# switch-rev2.net
KiCad netlist of a schematic drawn in EAGLE
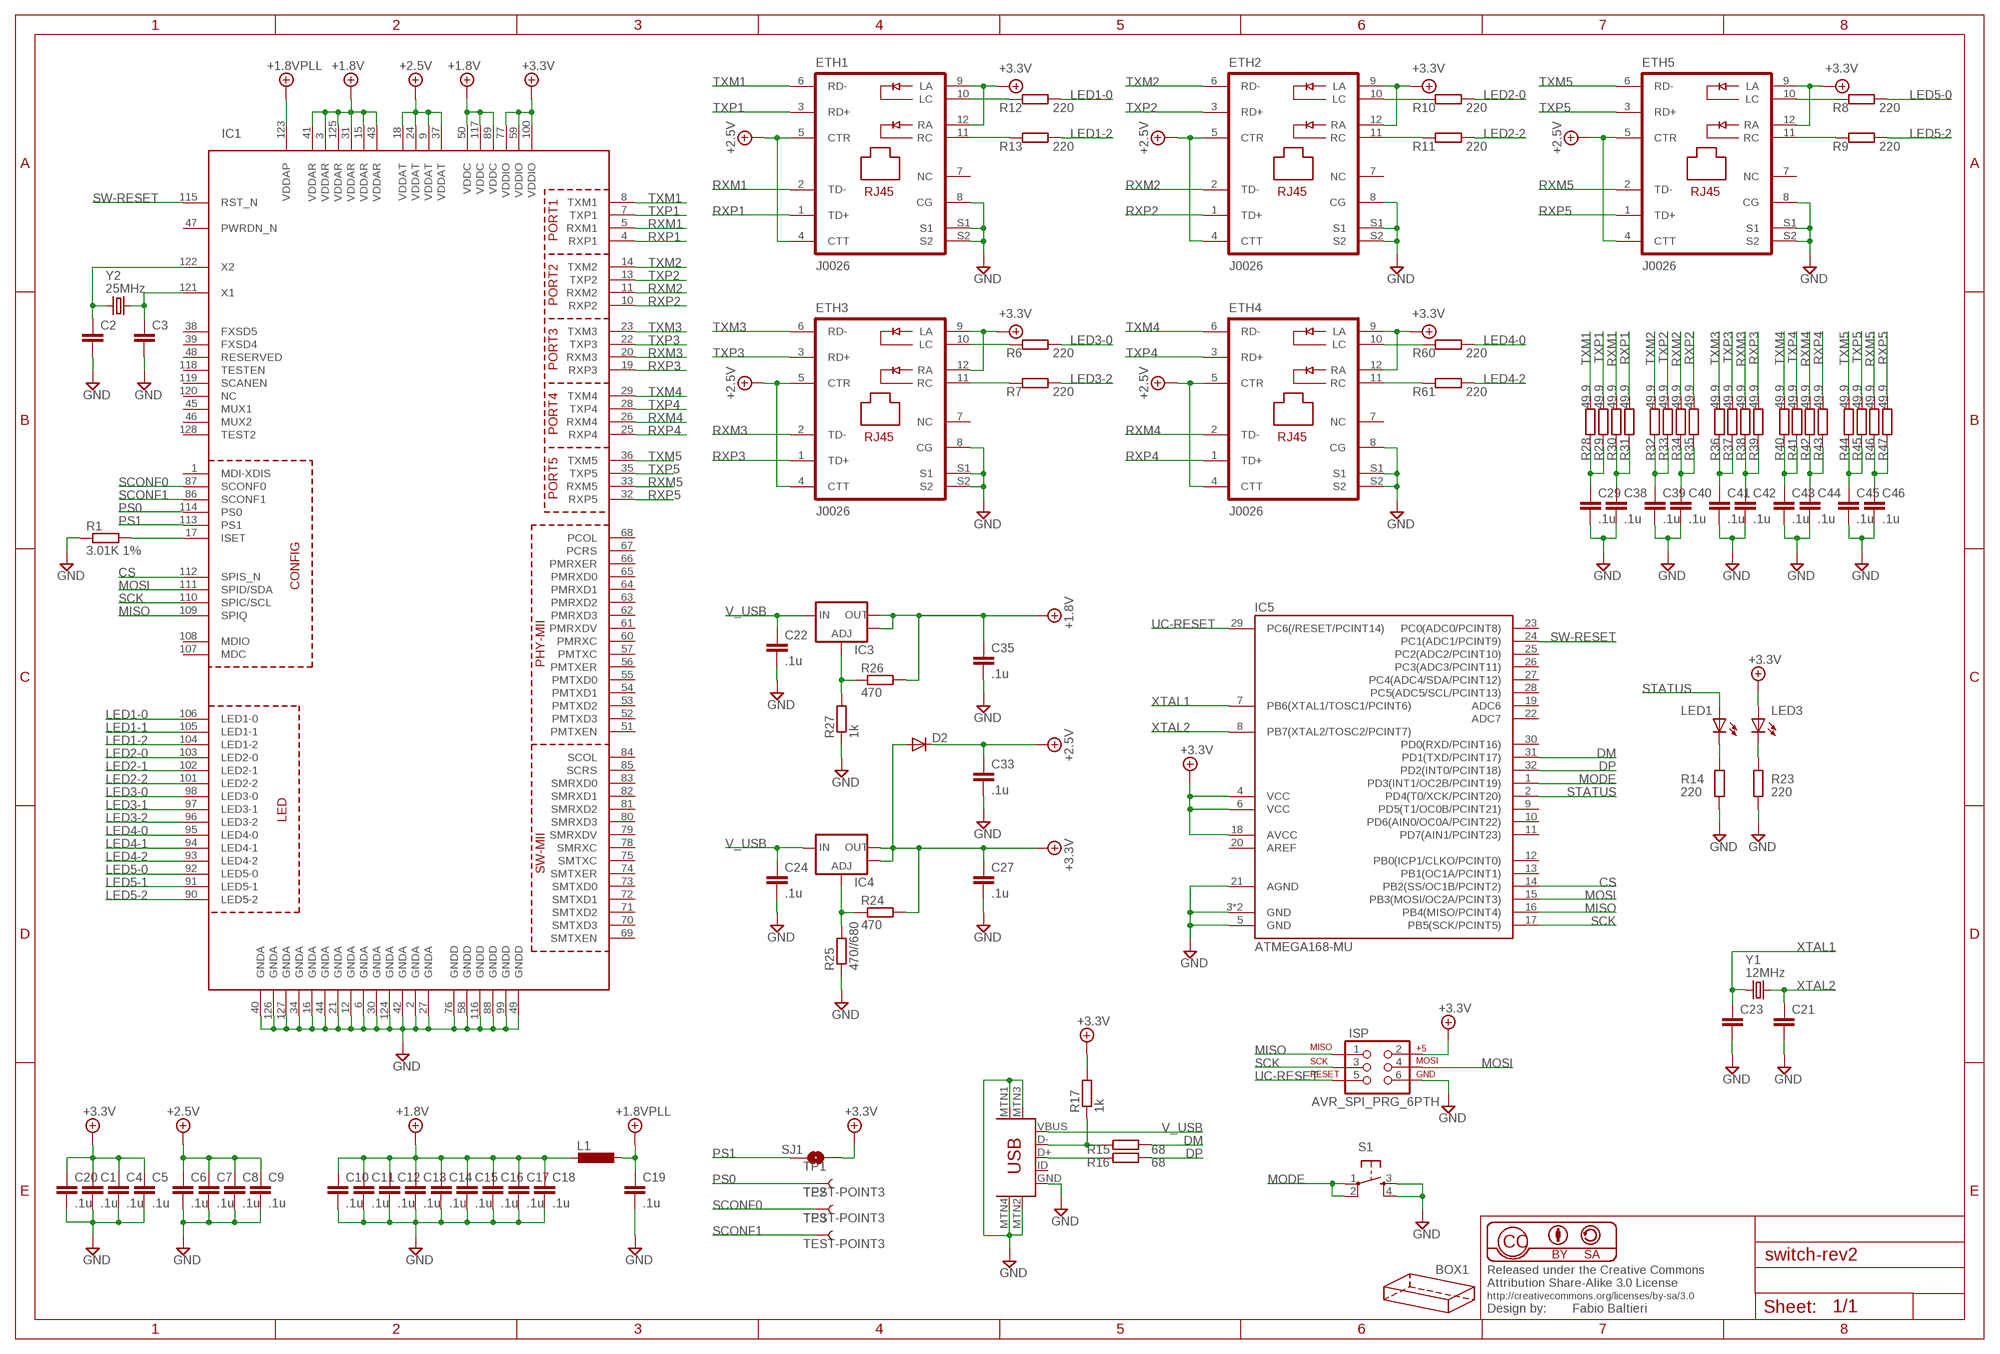
[diagram p0: schematic, sheet 1]

(export (version "E")
  (design (tool "Eeschema 10.0.6"))
  (components
    (comp (ref "BOX1")
      (value "HAMMOND-BOX-XXA")
      (footprint "eagle-import:1591XXA")
      (libsource (lib "eagle-import") (part "HAMMOND-BOX-XXA"))
    )
    (comp (ref "C1")
      (value ".1u")
      (footprint "eagle-import:C0805")
      (libsource (lib "eagle-import") (part "C-EUC0805"))
    )
    (comp (ref "C2")
      (value "C-EUC0805")
      (footprint "eagle-import:C0805")
      (libsource (lib "eagle-import") (part "C-EUC0805"))
    )
    (comp (ref "C3")
      (value "C-EUC0805")
      (footprint "eagle-import:C0805")
      (libsource (lib "eagle-import") (part "C-EUC0805"))
    )
    (comp (ref "C4")
      (value ".1u")
      (footprint "eagle-import:C0805")
      (libsource (lib "eagle-import") (part "C-EUC0805"))
    )
    (comp (ref "C5")
      (value ".1u")
      (footprint "eagle-import:C0805")
      (libsource (lib "eagle-import") (part "C-EUC0805"))
    )
    (comp (ref "C6")
      (value ".1u")
      (footprint "eagle-import:C0805")
      (libsource (lib "eagle-import") (part "C-EUC0805"))
    )
    (comp (ref "C7")
      (value ".1u")
      (footprint "eagle-import:C0805")
      (libsource (lib "eagle-import") (part "C-EUC0805"))
    )
    (comp (ref "C8")
      (value ".1u")
      (footprint "eagle-import:C0805")
      (libsource (lib "eagle-import") (part "C-EUC0805"))
    )
    (comp (ref "C9")
      (value ".1u")
      (footprint "eagle-import:C0805")
      (libsource (lib "eagle-import") (part "C-EUC0805"))
    )
    (comp (ref "C10")
      (value ".1u")
      (footprint "eagle-import:C0805")
      (libsource (lib "eagle-import") (part "C-EUC0805"))
    )
    (comp (ref "C11")
      (value ".1u")
      (footprint "eagle-import:C0805")
      (libsource (lib "eagle-import") (part "C-EUC0805"))
    )
    (comp (ref "C12")
      (value ".1u")
      (footprint "eagle-import:C0805")
      (libsource (lib "eagle-import") (part "C-EUC0805"))
    )
    (comp (ref "C13")
      (value ".1u")
      (footprint "eagle-import:C0805")
      (libsource (lib "eagle-import") (part "C-EUC0805"))
    )
    (comp (ref "C14")
      (value ".1u")
      (footprint "eagle-import:C0805")
      (libsource (lib "eagle-import") (part "C-EUC0805"))
    )
    (comp (ref "C15")
      (value ".1u")
      (footprint "eagle-import:C0805")
      (libsource (lib "eagle-import") (part "C-EUC0805"))
    )
    (comp (ref "C16")
      (value ".1u")
      (footprint "eagle-import:C0805")
      (libsource (lib "eagle-import") (part "C-EUC0805"))
    )
    (comp (ref "C17")
      (value ".1u")
      (footprint "eagle-import:C0805")
      (libsource (lib "eagle-import") (part "C-EUC0805"))
    )
    (comp (ref "C18")
      (value ".1u")
      (footprint "eagle-import:C0805")
      (libsource (lib "eagle-import") (part "C-EUC0805"))
    )
    (comp (ref "C19")
      (value ".1u")
      (footprint "eagle-import:C0805")
      (libsource (lib "eagle-import") (part "C-EUC0805"))
    )
    (comp (ref "C20")
      (value ".1u")
      (footprint "eagle-import:C0805")
      (libsource (lib "eagle-import") (part "C-EUC0805"))
    )
    (comp (ref "C21")
      (value "C-EUC0805")
      (footprint "eagle-import:C0805")
      (libsource (lib "eagle-import") (part "C-EUC0805"))
    )
    (comp (ref "C22")
      (value ".1u")
      (footprint "eagle-import:C0805")
      (libsource (lib "eagle-import") (part "C-EUC0805"))
    )
    (comp (ref "C23")
      (value "C-EUC0805")
      (footprint "eagle-import:C0805")
      (libsource (lib "eagle-import") (part "C-EUC0805"))
    )
    (comp (ref "C24")
      (value ".1u")
      (footprint "eagle-import:C0805")
      (libsource (lib "eagle-import") (part "C-EUC0805"))
    )
    (comp (ref "C27")
      (value ".1u")
      (footprint "eagle-import:C0805")
      (libsource (lib "eagle-import") (part "C-EUC0805"))
    )
    (comp (ref "C29")
      (value ".1u")
      (footprint "eagle-import:C0805")
      (libsource (lib "eagle-import") (part "C-EUC0805"))
    )
    (comp (ref "C33")
      (value ".1u")
      (footprint "eagle-import:C0805")
      (libsource (lib "eagle-import") (part "C-EUC0805"))
    )
    (comp (ref "C35")
      (value ".1u")
      (footprint "eagle-import:C0805")
      (libsource (lib "eagle-import") (part "C-EUC0805"))
    )
    (comp (ref "C38")
      (value ".1u")
      (footprint "eagle-import:C0805")
      (libsource (lib "eagle-import") (part "C-EUC0805"))
    )
    (comp (ref "C39")
      (value ".1u")
      (footprint "eagle-import:C0805")
      (libsource (lib "eagle-import") (part "C-EUC0805"))
    )
    (comp (ref "C40")
      (value ".1u")
      (footprint "eagle-import:C0805")
      (libsource (lib "eagle-import") (part "C-EUC0805"))
    )
    (comp (ref "C41")
      (value ".1u")
      (footprint "eagle-import:C0805")
      (libsource (lib "eagle-import") (part "C-EUC0805"))
    )
    (comp (ref "C42")
      (value ".1u")
      (footprint "eagle-import:C0805")
      (libsource (lib "eagle-import") (part "C-EUC0805"))
    )
    (comp (ref "C43")
      (value ".1u")
      (footprint "eagle-import:C0805")
      (libsource (lib "eagle-import") (part "C-EUC0805"))
    )
    (comp (ref "C44")
      (value ".1u")
      (footprint "eagle-import:C0805")
      (libsource (lib "eagle-import") (part "C-EUC0805"))
    )
    (comp (ref "C45")
      (value ".1u")
      (footprint "eagle-import:C0805")
      (libsource (lib "eagle-import") (part "C-EUC0805"))
    )
    (comp (ref "C46")
      (value ".1u")
      (footprint "eagle-import:C0805")
      (libsource (lib "eagle-import") (part "C-EUC0805"))
    )
    (comp (ref "D2")
      (value "DIODE-SMB")
      (footprint "eagle-import:SMB")
      (libsource (lib "eagle-import") (part "DIODE-SMB"))
    )
    (comp (ref "ETH1")
      (value "J0026")
      (footprint "eagle-import:PJ-J0")
      (libsource (lib "eagle-import") (part "J0026"))
    )
    (comp (ref "ETH2")
      (value "J0026")
      (footprint "eagle-import:PJ-J0")
      (libsource (lib "eagle-import") (part "J0026"))
    )
    (comp (ref "ETH3")
      (value "J0026")
      (footprint "eagle-import:PJ-J0")
      (libsource (lib "eagle-import") (part "J0026"))
    )
    (comp (ref "ETH4")
      (value "J0026")
      (footprint "eagle-import:PJ-J0")
      (libsource (lib "eagle-import") (part "J0026"))
    )
    (comp (ref "ETH5")
      (value "J0026")
      (footprint "eagle-import:PJ-J0")
      (libsource (lib "eagle-import") (part "J0026"))
    )
    (comp (ref "IC1")
      (value "KS8995MA")
      (footprint "eagle-import:PQFP128L")
      (libsource (lib "eagle-import") (part "KS8995MA"))
    )
    (comp (ref "IC3")
      (value "V_REG_LM1117SOT223")
      (footprint "eagle-import:SOT223")
      (libsource (lib "eagle-import") (part "V_REG_LM1117SOT223"))
    )
    (comp (ref "IC4")
      (value "V_REG_LM1117SOT223")
      (footprint "eagle-import:SOT223")
      (libsource (lib "eagle-import") (part "V_REG_LM1117SOT223"))
    )
    (comp (ref "IC5")
      (value "ATMEGA168-MU")
      (footprint "eagle-import:MLF32-TH")
      (libsource (lib "eagle-import") (part "ATMEGA168-MU"))
    )
    (comp (ref "ISP")
      (value "AVR_SPI_PRG_6PTH")
      (footprint "eagle-import:2X3")
      (libsource (lib "eagle-import") (part "AVR_SPI_PRG_6PTH"))
    )
    (comp (ref "L1")
      (value "L-EUL2012C")
      (footprint "eagle-import:L2012C")
      (libsource (lib "eagle-import") (part "L-EUL2012C"))
    )
    (comp (ref "LED1")
      (value "LEDCHIPLED_0603")
      (footprint "eagle-import:CHIPLED_0603")
      (libsource (lib "eagle-import") (part "LEDCHIPLED_0603"))
    )
    (comp (ref "LED3")
      (value "LEDCHIPLED_0603")
      (footprint "eagle-import:CHIPLED_0603")
      (libsource (lib "eagle-import") (part "LEDCHIPLED_0603"))
    )
    (comp (ref "R1")
      (value "3.01K 1%")
      (footprint "eagle-import:R0603")
      (libsource (lib "eagle-import") (part "R-EU_R0603"))
    )
    (comp (ref "R6")
      (value "220")
      (footprint "eagle-import:R0603")
      (libsource (lib "eagle-import") (part "R-EU_R0603"))
    )
    (comp (ref "R7")
      (value "220")
      (footprint "eagle-import:R0603")
      (libsource (lib "eagle-import") (part "R-EU_R0603"))
    )
    (comp (ref "R8")
      (value "220")
      (footprint "eagle-import:R0603")
      (libsource (lib "eagle-import") (part "R-EU_R0603"))
    )
    (comp (ref "R9")
      (value "220")
      (footprint "eagle-import:R0603")
      (libsource (lib "eagle-import") (part "R-EU_R0603"))
    )
    (comp (ref "R10")
      (value "220")
      (footprint "eagle-import:R0603")
      (libsource (lib "eagle-import") (part "R-EU_R0603"))
    )
    (comp (ref "R11")
      (value "220")
      (footprint "eagle-import:R0603")
      (libsource (lib "eagle-import") (part "R-EU_R0603"))
    )
    (comp (ref "R12")
      (value "220")
      (footprint "eagle-import:R0603")
      (libsource (lib "eagle-import") (part "R-EU_R0603"))
    )
    (comp (ref "R13")
      (value "220")
      (footprint "eagle-import:R0603")
      (libsource (lib "eagle-import") (part "R-EU_R0603"))
    )
    (comp (ref "R14")
      (value "220")
      (footprint "eagle-import:R0603")
      (libsource (lib "eagle-import") (part "R-EU_R0603"))
    )
    (comp (ref "R15")
      (value "68")
      (footprint "eagle-import:R0603")
      (libsource (lib "eagle-import") (part "R-EU_R0603"))
    )
    (comp (ref "R16")
      (value "68")
      (footprint "eagle-import:R0603")
      (libsource (lib "eagle-import") (part "R-EU_R0603"))
    )
    (comp (ref "R17")
      (value "1k")
      (footprint "eagle-import:R0603")
      (libsource (lib "eagle-import") (part "R-EU_R0603"))
    )
    (comp (ref "R23")
      (value "220")
      (footprint "eagle-import:R0603")
      (libsource (lib "eagle-import") (part "R-EU_R0603"))
    )
    (comp (ref "R24")
      (value "470")
      (footprint "eagle-import:R0603")
      (libsource (lib "eagle-import") (part "R-EU_R0603"))
    )
    (comp (ref "R25")
      (value "470//680")
      (footprint "eagle-import:R0603")
      (libsource (lib "eagle-import") (part "R-EU_R0603"))
    )
    (comp (ref "R26")
      (value "470")
      (footprint "eagle-import:R0603")
      (libsource (lib "eagle-import") (part "R-EU_R0603"))
    )
    (comp (ref "R27")
      (value "1k")
      (footprint "eagle-import:R0603")
      (libsource (lib "eagle-import") (part "R-EU_R0603"))
    )
    (comp (ref "R28")
      (value "49.9")
      (footprint "eagle-import:R0603")
      (libsource (lib "eagle-import") (part "R-EU_R0603"))
    )
    (comp (ref "R29")
      (value "49.9")
      (footprint "eagle-import:R0603")
      (libsource (lib "eagle-import") (part "R-EU_R0603"))
    )
    (comp (ref "R30")
      (value "49.9")
      (footprint "eagle-import:R0603")
      (libsource (lib "eagle-import") (part "R-EU_R0603"))
    )
    (comp (ref "R31")
      (value "49.9")
      (footprint "eagle-import:R0603")
      (libsource (lib "eagle-import") (part "R-EU_R0603"))
    )
    (comp (ref "R32")
      (value "49.9")
      (footprint "eagle-import:R0603")
      (libsource (lib "eagle-import") (part "R-EU_R0603"))
    )
    (comp (ref "R33")
      (value "49.9")
      (footprint "eagle-import:R0603")
      (libsource (lib "eagle-import") (part "R-EU_R0603"))
    )
    (comp (ref "R34")
      (value "49.9")
      (footprint "eagle-import:R0603")
      (libsource (lib "eagle-import") (part "R-EU_R0603"))
    )
    (comp (ref "R35")
      (value "49.9")
      (footprint "eagle-import:R0603")
      (libsource (lib "eagle-import") (part "R-EU_R0603"))
    )
    (comp (ref "R36")
      (value "49.9")
      (footprint "eagle-import:R0603")
      (libsource (lib "eagle-import") (part "R-EU_R0603"))
    )
    (comp (ref "R37")
      (value "49.9")
      (footprint "eagle-import:R0603")
      (libsource (lib "eagle-import") (part "R-EU_R0603"))
    )
    (comp (ref "R38")
      (value "49.9")
      (footprint "eagle-import:R0603")
      (libsource (lib "eagle-import") (part "R-EU_R0603"))
    )
    (comp (ref "R39")
      (value "49.9")
      (footprint "eagle-import:R0603")
      (libsource (lib "eagle-import") (part "R-EU_R0603"))
    )
    (comp (ref "R40")
      (value "49.9")
      (footprint "eagle-import:R0603")
      (libsource (lib "eagle-import") (part "R-EU_R0603"))
    )
    (comp (ref "R41")
      (value "49.9")
      (footprint "eagle-import:R0603")
      (libsource (lib "eagle-import") (part "R-EU_R0603"))
    )
    (comp (ref "R42")
      (value "49.9")
      (footprint "eagle-import:R0603")
      (libsource (lib "eagle-import") (part "R-EU_R0603"))
    )
    (comp (ref "R43")
      (value "49.9")
      (footprint "eagle-import:R0603")
      (libsource (lib "eagle-import") (part "R-EU_R0603"))
    )
    (comp (ref "R44")
      (value "49.9")
      (footprint "eagle-import:R0603")
      (libsource (lib "eagle-import") (part "R-EU_R0603"))
    )
    (comp (ref "R45")
      (value "49.9")
      (footprint "eagle-import:R0603")
      (libsource (lib "eagle-import") (part "R-EU_R0603"))
    )
    (comp (ref "R46")
      (value "49.9")
      (footprint "eagle-import:R0603")
      (libsource (lib "eagle-import") (part "R-EU_R0603"))
    )
    (comp (ref "R47")
      (value "49.9")
      (footprint "eagle-import:R0603")
      (libsource (lib "eagle-import") (part "R-EU_R0603"))
    )
    (comp (ref "R60")
      (value "220")
      (footprint "eagle-import:R0603")
      (libsource (lib "eagle-import") (part "R-EU_R0603"))
    )
    (comp (ref "R61")
      (value "220")
      (footprint "eagle-import:R0603")
      (libsource (lib "eagle-import") (part "R-EU_R0603"))
    )
    (comp (ref "S1")
      (value "TAC_SWITCHSMD")
      (footprint "eagle-import:TACTILE_SWITCH_SMD")
      (libsource (lib "eagle-import") (part "TAC_SWITCHSMD"))
    )
    (comp (ref "SJ1")
      (value "SOLDERJUMPERTRACE")
      (footprint "eagle-import:SJ_2S-TRACE")
      (libsource (lib "eagle-import") (part "SOLDERJUMPERTRACE"))
    )
    (comp (ref "TP1")
      (value "TEST-POINT3")
      (footprint "eagle-import:PAD.03X.03")
      (libsource (lib "eagle-import") (part "TEST-POINT3"))
    )
    (comp (ref "TP2")
      (value "TEST-POINT3")
      (footprint "eagle-import:PAD.03X.03")
      (libsource (lib "eagle-import") (part "TEST-POINT3"))
    )
    (comp (ref "TP3")
      (value "TEST-POINT3")
      (footprint "eagle-import:PAD.03X.03")
      (libsource (lib "eagle-import") (part "TEST-POINT3"))
    )
    (comp (ref "U$1")
      (value "USB-MINIB-5PIN")
      (footprint "eagle-import:USB-MINIB")
      (libsource (lib "eagle-import") (part "USB-MINIB-5PIN"))
    )
    (comp (ref "Y1")
      (value "12MHz")
      (footprint "eagle-import:CRYSTAL-SMD-5X3")
      (libsource (lib "eagle-import") (part "CRYSTAL5X3"))
    )
    (comp (ref "Y2")
      (value "25MHz")
      (footprint "eagle-import:CRYSTAL-SMD-5X3")
      (libsource (lib "eagle-import") (part "CRYSTAL5X3"))
    )
  )
  (nets
    (net (code "1") (name "+1.8V") (class "Default")
      (node (ref "C10") (pin "1") (pinfunction "1_1") (pintype "passive"))
      (node (ref "C11") (pin "1") (pinfunction "1_1") (pintype "passive"))
      (node (ref "C12") (pin "1") (pinfunction "1_1") (pintype "passive"))
      (node (ref "C13") (pin "1") (pinfunction "1_1") (pintype "passive"))
      (node (ref "C14") (pin "1") (pinfunction "1_1") (pintype "passive"))
      (node (ref "C15") (pin "1") (pinfunction "1_1") (pintype "passive"))
      (node (ref "C16") (pin "1") (pinfunction "1_1") (pintype "passive"))
      (node (ref "C17") (pin "1") (pinfunction "1_1") (pintype "passive"))
      (node (ref "C18") (pin "1") (pinfunction "1_1") (pintype "passive"))
      (node (ref "C35") (pin "1") (pinfunction "1_1") (pintype "passive"))
      (node (ref "IC1") (pin "117") (pinfunction "VDDC_117") (pintype "bidirectional"))
      (node (ref "IC1") (pin "125") (pinfunction "VDDAR_125") (pintype "bidirectional"))
      (node (ref "IC1") (pin "15") (pinfunction "VDDAR_15") (pintype "bidirectional"))
      (node (ref "IC1") (pin "3") (pinfunction "VDDAR_3") (pintype "bidirectional"))
      (node (ref "IC1") (pin "31") (pinfunction "VDDAR_31") (pintype "bidirectional"))
      (node (ref "IC1") (pin "41") (pinfunction "VDDAR_41") (pintype "bidirectional"))
      (node (ref "IC1") (pin "43") (pinfunction "VDDAR_43") (pintype "bidirectional"))
      (node (ref "IC1") (pin "50") (pinfunction "VDDC_50") (pintype "bidirectional"))
      (node (ref "IC1") (pin "89") (pinfunction "VDDC_89") (pintype "bidirectional"))
      (node (ref "IC3") (pin "2") (pinfunction "OUT_2") (pintype "output"))
      (node (ref "IC3") (pin "4") (pinfunction "OUT_4") (pintype "output"))
      (node (ref "L1") (pin "2") (pinfunction "2_2") (pintype "passive"))
      (node (ref "R26") (pin "2") (pinfunction "2_2") (pintype "passive"))
    )
    (net (code "2") (name "+1.8VPLL") (class "Default")
      (node (ref "C19") (pin "1") (pinfunction "1_1") (pintype "passive"))
      (node (ref "IC1") (pin "123") (pinfunction "VDDAP_123") (pintype "bidirectional"))
      (node (ref "L1") (pin "1") (pinfunction "1_1") (pintype "passive"))
    )
    (net (code "3") (name "+2.5V") (class "Default")
      (node (ref "C33") (pin "1") (pinfunction "1_1") (pintype "passive"))
      (node (ref "C6") (pin "1") (pinfunction "1_1") (pintype "passive"))
      (node (ref "C7") (pin "1") (pinfunction "1_1") (pintype "passive"))
      (node (ref "C8") (pin "1") (pinfunction "1_1") (pintype "passive"))
      (node (ref "C9") (pin "1") (pinfunction "1_1") (pintype "passive"))
      (node (ref "D2") (pin "C") (pinfunction "C_C") (pintype "passive"))
      (node (ref "ETH1") (pin "4") (pinfunction "CTT_4") (pintype "bidirectional"))
      (node (ref "ETH1") (pin "5") (pinfunction "CTR_5") (pintype "bidirectional"))
      (node (ref "ETH2") (pin "4") (pinfunction "CTT_4") (pintype "bidirectional"))
      (node (ref "ETH2") (pin "5") (pinfunction "CTR_5") (pintype "bidirectional"))
      (node (ref "ETH3") (pin "4") (pinfunction "CTT_4") (pintype "bidirectional"))
      (node (ref "ETH3") (pin "5") (pinfunction "CTR_5") (pintype "bidirectional"))
      (node (ref "ETH4") (pin "4") (pinfunction "CTT_4") (pintype "bidirectional"))
      (node (ref "ETH4") (pin "5") (pinfunction "CTR_5") (pintype "bidirectional"))
      (node (ref "ETH5") (pin "4") (pinfunction "CTT_4") (pintype "bidirectional"))
      (node (ref "ETH5") (pin "5") (pinfunction "CTR_5") (pintype "bidirectional"))
      (node (ref "IC1") (pin "18") (pinfunction "VDDAT_18") (pintype "bidirectional"))
      (node (ref "IC1") (pin "24") (pinfunction "VDDAT_24") (pintype "bidirectional"))
      (node (ref "IC1") (pin "37") (pinfunction "VDDAT_37") (pintype "bidirectional"))
      (node (ref "IC1") (pin "9") (pinfunction "VDDAT_9") (pintype "bidirectional"))
    )
    (net (code "4") (name "+3.3V") (class "Default")
      (node (ref "C1") (pin "1") (pinfunction "1_1") (pintype "passive"))
      (node (ref "C20") (pin "1") (pinfunction "1_1") (pintype "passive"))
      (node (ref "C27") (pin "1") (pinfunction "1_1") (pintype "passive"))
      (node (ref "C4") (pin "1") (pinfunction "1_1") (pintype "passive"))
      (node (ref "C5") (pin "1") (pinfunction "1_1") (pintype "passive"))
      (node (ref "D2") (pin "A") (pinfunction "A_A") (pintype "passive"))
      (node (ref "ETH1") (pin "12") (pinfunction "RA_12") (pintype "passive"))
      (node (ref "ETH1") (pin "9") (pinfunction "LA_9") (pintype "passive"))
      (node (ref "ETH2") (pin "12") (pinfunction "RA_12") (pintype "passive"))
      (node (ref "ETH2") (pin "9") (pinfunction "LA_9") (pintype "passive"))
      (node (ref "ETH3") (pin "12") (pinfunction "RA_12") (pintype "passive"))
      (node (ref "ETH3") (pin "9") (pinfunction "LA_9") (pintype "passive"))
      (node (ref "ETH4") (pin "12") (pinfunction "RA_12") (pintype "passive"))
      (node (ref "ETH4") (pin "9") (pinfunction "LA_9") (pintype "passive"))
      (node (ref "ETH5") (pin "12") (pinfunction "RA_12") (pintype "passive"))
      (node (ref "ETH5") (pin "9") (pinfunction "LA_9") (pintype "passive"))
      (node (ref "IC1") (pin "100") (pinfunction "VDDIO_100") (pintype "bidirectional"))
      (node (ref "IC1") (pin "59") (pinfunction "VDDIO_59") (pintype "bidirectional"))
      (node (ref "IC1") (pin "77") (pinfunction "VDDIO_77") (pintype "bidirectional"))
      (node (ref "IC4") (pin "2") (pinfunction "OUT_2") (pintype "output"))
      (node (ref "IC4") (pin "4") (pinfunction "OUT_4") (pintype "output"))
      (node (ref "IC5") (pin "18") (pinfunction "AVCC_18") (pintype "passive"))
      (node (ref "IC5") (pin "4") (pinfunction "VCC_4") (pintype "power_in"))
      (node (ref "IC5") (pin "6") (pinfunction "VCC_6") (pintype "power_in"))
      (node (ref "ISP") (pin "2") (pinfunction "2_2") (pintype "passive"))
      (node (ref "LED3") (pin "A") (pinfunction "A_A") (pintype "passive"))
      (node (ref "R17") (pin "2") (pinfunction "2_2") (pintype "passive"))
      (node (ref "R24") (pin "2") (pinfunction "2_2") (pintype "passive"))
      (node (ref "SJ1") (pin "2") (pinfunction "2_2") (pintype "passive"))
    )
    (net (code "5") (name "/CS") (class "Default")
      (node (ref "IC1") (pin "112") (pinfunction "SPIS_N_112") (pintype "bidirectional"))
      (node (ref "IC5") (pin "14") (pinfunction "PB2(SS/OC1B/PCINT2)_14") (pintype "bidirectional"))
    )
    (net (code "6") (name "/DM") (class "Default")
      (node (ref "IC5") (pin "31") (pinfunction "PD1(TXD/PCINT17)_31") (pintype "bidirectional"))
      (node (ref "R15") (pin "1") (pinfunction "1_1") (pintype "passive"))
    )
    (net (code "7") (name "/DP") (class "Default")
      (node (ref "IC5") (pin "32") (pinfunction "PD2(INT0/PCINT18)_32") (pintype "bidirectional"))
      (node (ref "R16") (pin "1") (pinfunction "1_1") (pintype "passive"))
    )
    (net (code "8") (name "/LED1-0") (class "Default")
      (node (ref "IC1") (pin "106") (pinfunction "LED1-0_106") (pintype "bidirectional"))
      (node (ref "R12") (pin "1") (pinfunction "1_1") (pintype "passive"))
    )
    (net (code "9") (name "/LED1-1") (class "Default")
      (node (ref "IC1") (pin "105") (pinfunction "LED1-1_105") (pintype "bidirectional"))
    )
    (net (code "10") (name "/LED1-2") (class "Default")
      (node (ref "IC1") (pin "104") (pinfunction "LED1-2_104") (pintype "bidirectional"))
      (node (ref "R13") (pin "1") (pinfunction "1_1") (pintype "passive"))
    )
    (net (code "11") (name "/LED2-0") (class "Default")
      (node (ref "IC1") (pin "103") (pinfunction "LED2-0_103") (pintype "bidirectional"))
      (node (ref "R10") (pin "1") (pinfunction "1_1") (pintype "passive"))
    )
    (net (code "12") (name "/LED2-1") (class "Default")
      (node (ref "IC1") (pin "102") (pinfunction "LED2-1_102") (pintype "bidirectional"))
    )
    (net (code "13") (name "/LED2-2") (class "Default")
      (node (ref "IC1") (pin "101") (pinfunction "LED2-2_101") (pintype "bidirectional"))
      (node (ref "R11") (pin "1") (pinfunction "1_1") (pintype "passive"))
    )
    (net (code "14") (name "/LED3-0") (class "Default")
      (node (ref "IC1") (pin "98") (pinfunction "LED3-0_98") (pintype "bidirectional"))
      (node (ref "R6") (pin "1") (pinfunction "1_1") (pintype "passive"))
    )
    (net (code "15") (name "/LED3-1") (class "Default")
      (node (ref "IC1") (pin "97") (pinfunction "LED3-1_97") (pintype "bidirectional"))
    )
    (net (code "16") (name "/LED3-2") (class "Default")
      (node (ref "IC1") (pin "96") (pinfunction "LED3-2_96") (pintype "bidirectional"))
      (node (ref "R7") (pin "1") (pinfunction "1_1") (pintype "passive"))
    )
    (net (code "17") (name "/LED4-0") (class "Default")
      (node (ref "IC1") (pin "95") (pinfunction "LED4-0_95") (pintype "bidirectional"))
      (node (ref "R60") (pin "1") (pinfunction "1_1") (pintype "passive"))
    )
    (net (code "18") (name "/LED4-1") (class "Default")
      (node (ref "IC1") (pin "94") (pinfunction "LED4-1_94") (pintype "bidirectional"))
    )
    (net (code "19") (name "/LED4-2") (class "Default")
      (node (ref "IC1") (pin "93") (pinfunction "LED4-2_93") (pintype "bidirectional"))
      (node (ref "R61") (pin "1") (pinfunction "1_1") (pintype "passive"))
    )
    (net (code "20") (name "/LED5-0") (class "Default")
      (node (ref "IC1") (pin "92") (pinfunction "LED5-0_92") (pintype "bidirectional"))
      (node (ref "R8") (pin "1") (pinfunction "1_1") (pintype "passive"))
    )
    (net (code "21") (name "/LED5-1") (class "Default")
      (node (ref "IC1") (pin "91") (pinfunction "LED5-1_91") (pintype "bidirectional"))
    )
    (net (code "22") (name "/LED5-2") (class "Default")
      (node (ref "IC1") (pin "90") (pinfunction "LED5-2_90") (pintype "bidirectional"))
      (node (ref "R9") (pin "1") (pinfunction "1_1") (pintype "passive"))
    )
    (net (code "23") (name "/MISO") (class "Default")
      (node (ref "IC1") (pin "109") (pinfunction "SPIQ_109") (pintype "bidirectional"))
      (node (ref "IC5") (pin "16") (pinfunction "PB4(MISO/PCINT4)_16") (pintype "bidirectional"))
      (node (ref "ISP") (pin "1") (pinfunction "1_1") (pintype "passive"))
    )
    (net (code "24") (name "/MODE") (class "Default")
      (node (ref "IC5") (pin "1") (pinfunction "PD3(INT1/OC2B/PCINT19)_1") (pintype "bidirectional"))
      (node (ref "S1") (pin "1") (pinfunction "1_1") (pintype "passive"))
      (node (ref "S1") (pin "2") (pinfunction "2_2") (pintype "passive"))
    )
    (net (code "25") (name "/MOSI") (class "Default")
      (node (ref "IC1") (pin "111") (pinfunction "SPID/SDA_111") (pintype "bidirectional"))
      (node (ref "IC5") (pin "15") (pinfunction "PB3(MOSI/OC2A/PCINT3)_15") (pintype "bidirectional"))
      (node (ref "ISP") (pin "4") (pinfunction "4_4") (pintype "passive"))
    )
    (net (code "26") (name "/PS0") (class "Default")
      (node (ref "IC1") (pin "114") (pinfunction "PS0_114") (pintype "bidirectional"))
      (node (ref "TP1") (pin "P$1") (pinfunction "1_P$1") (pintype "bidirectional"))
    )
    (net (code "27") (name "/PS1") (class "Default")
      (node (ref "IC1") (pin "113") (pinfunction "PS1_113") (pintype "bidirectional"))
      (node (ref "SJ1") (pin "1") (pinfunction "1_1") (pintype "passive"))
    )
    (net (code "28") (name "/RXM1") (class "Default")
      (node (ref "ETH1") (pin "2") (pinfunction "TD-_2") (pintype "bidirectional"))
      (node (ref "IC1") (pin "5") (pinfunction "RXM1_5") (pintype "bidirectional"))
      (node (ref "R30") (pin "2") (pinfunction "2_2") (pintype "passive"))
    )
    (net (code "29") (name "/RXM2") (class "Default")
      (node (ref "ETH2") (pin "2") (pinfunction "TD-_2") (pintype "bidirectional"))
      (node (ref "IC1") (pin "11") (pinfunction "RXM2_11") (pintype "bidirectional"))
      (node (ref "R34") (pin "2") (pinfunction "2_2") (pintype "passive"))
    )
    (net (code "30") (name "/RXM3") (class "Default")
      (node (ref "ETH3") (pin "2") (pinfunction "TD-_2") (pintype "bidirectional"))
      (node (ref "IC1") (pin "20") (pinfunction "RXM3_20") (pintype "bidirectional"))
      (node (ref "R38") (pin "2") (pinfunction "2_2") (pintype "passive"))
    )
    (net (code "31") (name "/RXM4") (class "Default")
      (node (ref "ETH4") (pin "2") (pinfunction "TD-_2") (pintype "bidirectional"))
      (node (ref "IC1") (pin "26") (pinfunction "RXM4_26") (pintype "bidirectional"))
      (node (ref "R42") (pin "2") (pinfunction "2_2") (pintype "passive"))
    )
    (net (code "32") (name "/RXM5") (class "Default")
      (node (ref "ETH5") (pin "2") (pinfunction "TD-_2") (pintype "bidirectional"))
      (node (ref "IC1") (pin "33") (pinfunction "RXM5_33") (pintype "bidirectional"))
      (node (ref "R46") (pin "2") (pinfunction "2_2") (pintype "passive"))
    )
    (net (code "33") (name "/RXP1") (class "Default")
      (node (ref "ETH1") (pin "1") (pinfunction "TD+_1") (pintype "bidirectional"))
      (node (ref "IC1") (pin "4") (pinfunction "RXP1_4") (pintype "bidirectional"))
      (node (ref "R31") (pin "2") (pinfunction "2_2") (pintype "passive"))
    )
    (net (code "34") (name "/RXP2") (class "Default")
      (node (ref "ETH2") (pin "1") (pinfunction "TD+_1") (pintype "bidirectional"))
      (node (ref "IC1") (pin "10") (pinfunction "RXP2_10") (pintype "bidirectional"))
      (node (ref "R35") (pin "2") (pinfunction "2_2") (pintype "passive"))
    )
    (net (code "35") (name "/RXP3") (class "Default")
      (node (ref "ETH3") (pin "1") (pinfunction "TD+_1") (pintype "bidirectional"))
      (node (ref "IC1") (pin "19") (pinfunction "RXP3_19") (pintype "bidirectional"))
      (node (ref "R39") (pin "2") (pinfunction "2_2") (pintype "passive"))
    )
    (net (code "36") (name "/RXP4") (class "Default")
      (node (ref "ETH4") (pin "1") (pinfunction "TD+_1") (pintype "bidirectional"))
      (node (ref "IC1") (pin "25") (pinfunction "RXP4_25") (pintype "bidirectional"))
      (node (ref "R43") (pin "2") (pinfunction "2_2") (pintype "passive"))
    )
    (net (code "37") (name "/RXP5") (class "Default")
      (node (ref "ETH5") (pin "1") (pinfunction "TD+_1") (pintype "bidirectional"))
      (node (ref "IC1") (pin "32") (pinfunction "RXP5_32") (pintype "bidirectional"))
      (node (ref "R47") (pin "2") (pinfunction "2_2") (pintype "passive"))
    )
    (net (code "38") (name "/SCK") (class "Default")
      (node (ref "IC1") (pin "110") (pinfunction "SPIC/SCL_110") (pintype "bidirectional"))
      (node (ref "IC5") (pin "17") (pinfunction "PB5(SCK/PCINT5)_17") (pintype "bidirectional"))
      (node (ref "ISP") (pin "3") (pinfunction "3_3") (pintype "passive"))
    )
    (net (code "39") (name "/SCONF0") (class "Default")
      (node (ref "IC1") (pin "87") (pinfunction "SCONF0_87") (pintype "bidirectional"))
      (node (ref "TP2") (pin "P$1") (pinfunction "1_P$1") (pintype "bidirectional"))
    )
    (net (code "40") (name "/SCONF1") (class "Default")
      (node (ref "IC1") (pin "86") (pinfunction "SCONF1_86") (pintype "bidirectional"))
      (node (ref "TP3") (pin "P$1") (pinfunction "1_P$1") (pintype "bidirectional"))
    )
    (net (code "41") (name "/STATUS") (class "Default")
      (node (ref "IC5") (pin "2") (pinfunction "PD4(T0/XCK/PCINT20)_2") (pintype "bidirectional"))
      (node (ref "LED1") (pin "A") (pinfunction "A_A") (pintype "passive"))
    )
    (net (code "42") (name "/SW-RESET") (class "Default")
      (node (ref "IC1") (pin "115") (pinfunction "RST_N_115") (pintype "bidirectional"))
      (node (ref "IC5") (pin "24") (pinfunction "PC1(ADC1/PCINT9)_24") (pintype "bidirectional"))
    )
    (net (code "43") (name "/TXM1") (class "Default")
      (node (ref "ETH1") (pin "6") (pinfunction "RD-_6") (pintype "bidirectional"))
      (node (ref "IC1") (pin "8") (pinfunction "TXM1_8") (pintype "bidirectional"))
      (node (ref "R28") (pin "2") (pinfunction "2_2") (pintype "passive"))
    )
    (net (code "44") (name "/TXM2") (class "Default")
      (node (ref "ETH2") (pin "6") (pinfunction "RD-_6") (pintype "bidirectional"))
      (node (ref "IC1") (pin "14") (pinfunction "TXM2_14") (pintype "bidirectional"))
      (node (ref "R32") (pin "2") (pinfunction "2_2") (pintype "passive"))
    )
    (net (code "45") (name "/TXM3") (class "Default")
      (node (ref "ETH3") (pin "6") (pinfunction "RD-_6") (pintype "bidirectional"))
      (node (ref "IC1") (pin "23") (pinfunction "TXM3_23") (pintype "bidirectional"))
      (node (ref "R36") (pin "2") (pinfunction "2_2") (pintype "passive"))
    )
    (net (code "46") (name "/TXM4") (class "Default")
      (node (ref "ETH4") (pin "6") (pinfunction "RD-_6") (pintype "bidirectional"))
      (node (ref "IC1") (pin "29") (pinfunction "TXM4_29") (pintype "bidirectional"))
      (node (ref "R40") (pin "2") (pinfunction "2_2") (pintype "passive"))
    )
    (net (code "47") (name "/TXM5") (class "Default")
      (node (ref "ETH5") (pin "6") (pinfunction "RD-_6") (pintype "bidirectional"))
      (node (ref "IC1") (pin "36") (pinfunction "TXM5_36") (pintype "bidirectional"))
      (node (ref "R44") (pin "2") (pinfunction "2_2") (pintype "passive"))
    )
    (net (code "48") (name "/TXP1") (class "Default")
      (node (ref "ETH1") (pin "3") (pinfunction "RD+_3") (pintype "bidirectional"))
      (node (ref "IC1") (pin "7") (pinfunction "TXP1_7") (pintype "bidirectional"))
      (node (ref "R29") (pin "2") (pinfunction "2_2") (pintype "passive"))
    )
    (net (code "49") (name "/TXP2") (class "Default")
      (node (ref "ETH2") (pin "3") (pinfunction "RD+_3") (pintype "bidirectional"))
      (node (ref "IC1") (pin "13") (pinfunction "TXP2_13") (pintype "bidirectional"))
      (node (ref "R33") (pin "2") (pinfunction "2_2") (pintype "passive"))
    )
    (net (code "50") (name "/TXP3") (class "Default")
      (node (ref "ETH3") (pin "3") (pinfunction "RD+_3") (pintype "bidirectional"))
      (node (ref "IC1") (pin "22") (pinfunction "TXP3_22") (pintype "bidirectional"))
      (node (ref "R37") (pin "2") (pinfunction "2_2") (pintype "passive"))
    )
    (net (code "51") (name "/TXP4") (class "Default")
      (node (ref "ETH4") (pin "3") (pinfunction "RD+_3") (pintype "bidirectional"))
      (node (ref "IC1") (pin "28") (pinfunction "TXP4_28") (pintype "bidirectional"))
      (node (ref "R41") (pin "2") (pinfunction "2_2") (pintype "passive"))
    )
    (net (code "52") (name "/TXP5") (class "Default")
      (node (ref "ETH5") (pin "3") (pinfunction "RD+_3") (pintype "bidirectional"))
      (node (ref "IC1") (pin "35") (pinfunction "TXP5_35") (pintype "bidirectional"))
      (node (ref "R45") (pin "2") (pinfunction "2_2") (pintype "passive"))
    )
    (net (code "53") (name "/UC-RESET") (class "Default")
      (node (ref "IC5") (pin "29") (pinfunction "PC6(/RESET/PCINT14)_29") (pintype "bidirectional"))
      (node (ref "ISP") (pin "5") (pinfunction "5_5") (pintype "passive"))
    )
    (net (code "54") (name "/V_USB") (class "Default")
      (node (ref "C22") (pin "1") (pinfunction "1_1") (pintype "passive"))
      (node (ref "C24") (pin "1") (pinfunction "1_1") (pintype "passive"))
      (node (ref "IC3") (pin "3") (pinfunction "IN_3") (pintype "input"))
      (node (ref "IC4") (pin "3") (pinfunction "IN_3") (pintype "input"))
      (node (ref "U$1") (pin "VBUS") (pinfunction "VBUS_VBUS") (pintype "bidirectional"))
    )
    (net (code "55") (name "/XTAL1") (class "Default")
      (node (ref "C23") (pin "1") (pinfunction "1_1") (pintype "passive"))
      (node (ref "IC5") (pin "7") (pinfunction "PB6(XTAL1/TOSC1/PCINT6)_7") (pintype "bidirectional"))
      (node (ref "Y1") (pin "1") (pinfunction "1_1") (pintype "passive"))
    )
    (net (code "56") (name "/XTAL2") (class "Default")
      (node (ref "C21") (pin "1") (pinfunction "1_1") (pintype "passive"))
      (node (ref "IC5") (pin "8") (pinfunction "PB7(XTAL2/TOSC2/PCINT7)_8") (pintype "bidirectional"))
      (node (ref "Y1") (pin "3") (pinfunction "2_3") (pintype "passive"))
    )
    (net (code "57") (name "GND") (class "Default")
      (node (ref "C1") (pin "2") (pinfunction "2_2") (pintype "passive"))
      (node (ref "C10") (pin "2") (pinfunction "2_2") (pintype "passive"))
      (node (ref "C11") (pin "2") (pinfunction "2_2") (pintype "passive"))
      (node (ref "C12") (pin "2") (pinfunction "2_2") (pintype "passive"))
      (node (ref "C13") (pin "2") (pinfunction "2_2") (pintype "passive"))
      (node (ref "C14") (pin "2") (pinfunction "2_2") (pintype "passive"))
      (node (ref "C15") (pin "2") (pinfunction "2_2") (pintype "passive"))
      (node (ref "C16") (pin "2") (pinfunction "2_2") (pintype "passive"))
      (node (ref "C17") (pin "2") (pinfunction "2_2") (pintype "passive"))
      (node (ref "C18") (pin "2") (pinfunction "2_2") (pintype "passive"))
      (node (ref "C19") (pin "2") (pinfunction "2_2") (pintype "passive"))
      (node (ref "C2") (pin "2") (pinfunction "2_2") (pintype "passive"))
      (node (ref "C20") (pin "2") (pinfunction "2_2") (pintype "passive"))
      (node (ref "C21") (pin "2") (pinfunction "2_2") (pintype "passive"))
      (node (ref "C22") (pin "2") (pinfunction "2_2") (pintype "passive"))
      (node (ref "C23") (pin "2") (pinfunction "2_2") (pintype "passive"))
      (node (ref "C24") (pin "2") (pinfunction "2_2") (pintype "passive"))
      (node (ref "C27") (pin "2") (pinfunction "2_2") (pintype "passive"))
      (node (ref "C29") (pin "2") (pinfunction "2_2") (pintype "passive"))
      (node (ref "C3") (pin "2") (pinfunction "2_2") (pintype "passive"))
      (node (ref "C33") (pin "2") (pinfunction "2_2") (pintype "passive"))
      (node (ref "C35") (pin "2") (pinfunction "2_2") (pintype "passive"))
      (node (ref "C38") (pin "2") (pinfunction "2_2") (pintype "passive"))
      (node (ref "C39") (pin "2") (pinfunction "2_2") (pintype "passive"))
      (node (ref "C4") (pin "2") (pinfunction "2_2") (pintype "passive"))
      (node (ref "C40") (pin "2") (pinfunction "2_2") (pintype "passive"))
      (node (ref "C41") (pin "2") (pinfunction "2_2") (pintype "passive"))
      (node (ref "C42") (pin "2") (pinfunction "2_2") (pintype "passive"))
      (node (ref "C43") (pin "2") (pinfunction "2_2") (pintype "passive"))
      (node (ref "C44") (pin "2") (pinfunction "2_2") (pintype "passive"))
      (node (ref "C45") (pin "2") (pinfunction "2_2") (pintype "passive"))
      (node (ref "C46") (pin "2") (pinfunction "2_2") (pintype "passive"))
      (node (ref "C5") (pin "2") (pinfunction "2_2") (pintype "passive"))
      (node (ref "C6") (pin "2") (pinfunction "2_2") (pintype "passive"))
      (node (ref "C7") (pin "2") (pinfunction "2_2") (pintype "passive"))
      (node (ref "C8") (pin "2") (pinfunction "2_2") (pintype "passive"))
      (node (ref "C9") (pin "2") (pinfunction "2_2") (pintype "passive"))
      (node (ref "ETH1") (pin "8") (pinfunction "CG_8") (pintype "passive"))
      (node (ref "ETH1") (pin "S1") (pinfunction "S1_S1") (pintype "passive"))
      (node (ref "ETH1") (pin "S2") (pinfunction "S2_S2") (pintype "passive"))
      (node (ref "ETH2") (pin "8") (pinfunction "CG_8") (pintype "passive"))
      (node (ref "ETH2") (pin "S1") (pinfunction "S1_S1") (pintype "passive"))
      (node (ref "ETH2") (pin "S2") (pinfunction "S2_S2") (pintype "passive"))
      (node (ref "ETH3") (pin "8") (pinfunction "CG_8") (pintype "passive"))
      (node (ref "ETH3") (pin "S1") (pinfunction "S1_S1") (pintype "passive"))
      (node (ref "ETH3") (pin "S2") (pinfunction "S2_S2") (pintype "passive"))
      (node (ref "ETH4") (pin "8") (pinfunction "CG_8") (pintype "passive"))
      (node (ref "ETH4") (pin "S1") (pinfunction "S1_S1") (pintype "passive"))
      (node (ref "ETH4") (pin "S2") (pinfunction "S2_S2") (pintype "passive"))
      (node (ref "ETH5") (pin "8") (pinfunction "CG_8") (pintype "passive"))
      (node (ref "ETH5") (pin "S1") (pinfunction "S1_S1") (pintype "passive"))
      (node (ref "ETH5") (pin "S2") (pinfunction "S2_S2") (pintype "passive"))
      (node (ref "IC1") (pin "116") (pinfunction "GNDD_116") (pintype "bidirectional"))
      (node (ref "IC1") (pin "12") (pinfunction "GNDA_12") (pintype "bidirectional"))
      (node (ref "IC1") (pin "124") (pinfunction "GNDA_124") (pintype "bidirectional"))
      (node (ref "IC1") (pin "126") (pinfunction "GNDA_126") (pintype "bidirectional"))
      (node (ref "IC1") (pin "127") (pinfunction "GNDA_127") (pintype "bidirectional"))
      (node (ref "IC1") (pin "16") (pinfunction "GNDA_16") (pintype "bidirectional"))
      (node (ref "IC1") (pin "2") (pinfunction "GNDA_2") (pintype "bidirectional"))
      (node (ref "IC1") (pin "21") (pinfunction "GNDA_21") (pintype "bidirectional"))
      (node (ref "IC1") (pin "27") (pinfunction "GNDA_27") (pintype "bidirectional"))
      (node (ref "IC1") (pin "30") (pinfunction "GNDA_30") (pintype "bidirectional"))
      (node (ref "IC1") (pin "34") (pinfunction "GNDA_34") (pintype "bidirectional"))
      (node (ref "IC1") (pin "40") (pinfunction "GNDA_40") (pintype "bidirectional"))
      (node (ref "IC1") (pin "42") (pinfunction "GNDA_42") (pintype "bidirectional"))
      (node (ref "IC1") (pin "44") (pinfunction "GNDA_44") (pintype "bidirectional"))
      (node (ref "IC1") (pin "49") (pinfunction "GNDD_49") (pintype "bidirectional"))
      (node (ref "IC1") (pin "58") (pinfunction "GNDD_58") (pintype "bidirectional"))
      (node (ref "IC1") (pin "6") (pinfunction "GNDA_6") (pintype "bidirectional"))
      (node (ref "IC1") (pin "76") (pinfunction "GNDD_76") (pintype "bidirectional"))
      (node (ref "IC1") (pin "88") (pinfunction "GNDD_88") (pintype "bidirectional"))
      (node (ref "IC1") (pin "99") (pinfunction "GNDD_99") (pintype "bidirectional"))
      (node (ref "IC5") (pin "21") (pinfunction "AGND_21") (pintype "power_in"))
      (node (ref "IC5") (pin "3") (pinfunction "GND_3") (pintype "power_in"))
      (node (ref "IC5") (pin "5") (pinfunction "GND_5") (pintype "power_in"))
      (node (ref "IC5") (pin "TH") (pinfunction "GND_TH") (pintype "power_in"))
      (node (ref "ISP") (pin "6") (pinfunction "6_6") (pintype "passive"))
      (node (ref "R1") (pin "1") (pinfunction "1_1") (pintype "passive"))
      (node (ref "R14") (pin "1") (pinfunction "1_1") (pintype "passive"))
      (node (ref "R23") (pin "1") (pinfunction "1_1") (pintype "passive"))
      (node (ref "R25") (pin "1") (pinfunction "1_1") (pintype "passive"))
      (node (ref "R27") (pin "1") (pinfunction "1_1") (pintype "passive"))
      (node (ref "S1") (pin "3") (pinfunction "3_3") (pintype "passive"))
      (node (ref "S1") (pin "4") (pinfunction "4_4") (pintype "passive"))
      (node (ref "U$1") (pin "GND") (pinfunction "GND_GND") (pintype "bidirectional"))
      (node (ref "U$1") (pin "MTN1") (pinfunction "MTN2_MTN1") (pintype "bidirectional"))
      (node (ref "U$1") (pin "MTN2") (pinfunction "MTN3_MTN2") (pintype "bidirectional"))
      (node (ref "U$1") (pin "MTN3") (pinfunction "MTN1_MTN3") (pintype "bidirectional"))
      (node (ref "U$1") (pin "MTN4") (pinfunction "MTN4_MTN4") (pintype "bidirectional"))
    )
    (net (code "58") (name "Net-(C29-Pad1)") (class "Default")
      (node (ref "C29") (pin "1") (pinfunction "1_1") (pintype "passive"))
      (node (ref "R28") (pin "1") (pinfunction "1_1") (pintype "passive"))
      (node (ref "R29") (pin "1") (pinfunction "1_1") (pintype "passive"))
    )
    (net (code "59") (name "Net-(C38-Pad1)") (class "Default")
      (node (ref "C38") (pin "1") (pinfunction "1_1") (pintype "passive"))
      (node (ref "R30") (pin "1") (pinfunction "1_1") (pintype "passive"))
      (node (ref "R31") (pin "1") (pinfunction "1_1") (pintype "passive"))
    )
    (net (code "60") (name "Net-(C39-Pad1)") (class "Default")
      (node (ref "C39") (pin "1") (pinfunction "1_1") (pintype "passive"))
      (node (ref "R32") (pin "1") (pinfunction "1_1") (pintype "passive"))
      (node (ref "R33") (pin "1") (pinfunction "1_1") (pintype "passive"))
    )
    (net (code "61") (name "Net-(C40-Pad1)") (class "Default")
      (node (ref "C40") (pin "1") (pinfunction "1_1") (pintype "passive"))
      (node (ref "R34") (pin "1") (pinfunction "1_1") (pintype "passive"))
      (node (ref "R35") (pin "1") (pinfunction "1_1") (pintype "passive"))
    )
    (net (code "62") (name "Net-(C41-Pad1)") (class "Default")
      (node (ref "C41") (pin "1") (pinfunction "1_1") (pintype "passive"))
      (node (ref "R36") (pin "1") (pinfunction "1_1") (pintype "passive"))
      (node (ref "R37") (pin "1") (pinfunction "1_1") (pintype "passive"))
    )
    (net (code "63") (name "Net-(C42-Pad1)") (class "Default")
      (node (ref "C42") (pin "1") (pinfunction "1_1") (pintype "passive"))
      (node (ref "R38") (pin "1") (pinfunction "1_1") (pintype "passive"))
      (node (ref "R39") (pin "1") (pinfunction "1_1") (pintype "passive"))
    )
    (net (code "64") (name "Net-(C43-Pad1)") (class "Default")
      (node (ref "C43") (pin "1") (pinfunction "1_1") (pintype "passive"))
      (node (ref "R40") (pin "1") (pinfunction "1_1") (pintype "passive"))
      (node (ref "R41") (pin "1") (pinfunction "1_1") (pintype "passive"))
    )
    (net (code "65") (name "Net-(C44-Pad1)") (class "Default")
      (node (ref "C44") (pin "1") (pinfunction "1_1") (pintype "passive"))
      (node (ref "R42") (pin "1") (pinfunction "1_1") (pintype "passive"))
      (node (ref "R43") (pin "1") (pinfunction "1_1") (pintype "passive"))
    )
    (net (code "66") (name "Net-(C45-Pad1)") (class "Default")
      (node (ref "C45") (pin "1") (pinfunction "1_1") (pintype "passive"))
      (node (ref "R44") (pin "1") (pinfunction "1_1") (pintype "passive"))
      (node (ref "R45") (pin "1") (pinfunction "1_1") (pintype "passive"))
    )
    (net (code "67") (name "Net-(C46-Pad1)") (class "Default")
      (node (ref "C46") (pin "1") (pinfunction "1_1") (pintype "passive"))
      (node (ref "R46") (pin "1") (pinfunction "1_1") (pintype "passive"))
      (node (ref "R47") (pin "1") (pinfunction "1_1") (pintype "passive"))
    )
    (net (code "68") (name "Net-(ETH1-LC)") (class "Default")
      (node (ref "ETH1") (pin "10") (pinfunction "LC_10") (pintype "passive"))
      (node (ref "R12") (pin "2") (pinfunction "2_2") (pintype "passive"))
    )
    (net (code "69") (name "Net-(ETH1-RC)") (class "Default")
      (node (ref "ETH1") (pin "11") (pinfunction "RC_11") (pintype "passive"))
      (node (ref "R13") (pin "2") (pinfunction "2_2") (pintype "passive"))
    )
    (net (code "70") (name "Net-(ETH2-LC)") (class "Default")
      (node (ref "ETH2") (pin "10") (pinfunction "LC_10") (pintype "passive"))
      (node (ref "R10") (pin "2") (pinfunction "2_2") (pintype "passive"))
    )
    (net (code "71") (name "Net-(ETH2-RC)") (class "Default")
      (node (ref "ETH2") (pin "11") (pinfunction "RC_11") (pintype "passive"))
      (node (ref "R11") (pin "2") (pinfunction "2_2") (pintype "passive"))
    )
    (net (code "72") (name "Net-(ETH3-LC)") (class "Default")
      (node (ref "ETH3") (pin "10") (pinfunction "LC_10") (pintype "passive"))
      (node (ref "R6") (pin "2") (pinfunction "2_2") (pintype "passive"))
    )
    (net (code "73") (name "Net-(ETH3-RC)") (class "Default")
      (node (ref "ETH3") (pin "11") (pinfunction "RC_11") (pintype "passive"))
      (node (ref "R7") (pin "2") (pinfunction "2_2") (pintype "passive"))
    )
    (net (code "74") (name "Net-(ETH4-LC)") (class "Default")
      (node (ref "ETH4") (pin "10") (pinfunction "LC_10") (pintype "passive"))
      (node (ref "R60") (pin "2") (pinfunction "2_2") (pintype "passive"))
    )
    (net (code "75") (name "Net-(ETH4-RC)") (class "Default")
      (node (ref "ETH4") (pin "11") (pinfunction "RC_11") (pintype "passive"))
      (node (ref "R61") (pin "2") (pinfunction "2_2") (pintype "passive"))
    )
    (net (code "76") (name "Net-(ETH5-LC)") (class "Default")
      (node (ref "ETH5") (pin "10") (pinfunction "LC_10") (pintype "passive"))
      (node (ref "R8") (pin "2") (pinfunction "2_2") (pintype "passive"))
    )
    (net (code "77") (name "Net-(ETH5-RC)") (class "Default")
      (node (ref "ETH5") (pin "11") (pinfunction "RC_11") (pintype "passive"))
      (node (ref "R9") (pin "2") (pinfunction "2_2") (pintype "passive"))
    )
    (net (code "78") (name "Net-(IC1-ISET)") (class "Default")
      (node (ref "IC1") (pin "17") (pinfunction "ISET_17") (pintype "bidirectional"))
      (node (ref "R1") (pin "2") (pinfunction "2_2") (pintype "passive"))
    )
    (net (code "79") (name "Net-(IC1-X1)") (class "Default")
      (node (ref "C3") (pin "1") (pinfunction "1_1") (pintype "passive"))
      (node (ref "IC1") (pin "121") (pinfunction "X1_121") (pintype "bidirectional"))
      (node (ref "Y2") (pin "3") (pinfunction "2_3") (pintype "passive"))
    )
    (net (code "80") (name "Net-(IC1-X2)") (class "Default")
      (node (ref "C2") (pin "1") (pinfunction "1_1") (pintype "passive"))
      (node (ref "IC1") (pin "122") (pinfunction "X2_122") (pintype "bidirectional"))
      (node (ref "Y2") (pin "1") (pinfunction "1_1") (pintype "passive"))
    )
    (net (code "81") (name "Net-(IC3-ADJ)") (class "Default")
      (node (ref "IC3") (pin "1") (pinfunction "ADJ_1") (pintype "input"))
      (node (ref "R26") (pin "1") (pinfunction "1_1") (pintype "passive"))
      (node (ref "R27") (pin "2") (pinfunction "2_2") (pintype "passive"))
    )
    (net (code "82") (name "Net-(IC4-ADJ)") (class "Default")
      (node (ref "IC4") (pin "1") (pinfunction "ADJ_1") (pintype "input"))
      (node (ref "R24") (pin "1") (pinfunction "1_1") (pintype "passive"))
      (node (ref "R25") (pin "2") (pinfunction "2_2") (pintype "passive"))
    )
    (net (code "83") (name "Net-(LED1-PadC)") (class "Default")
      (node (ref "LED1") (pin "C") (pinfunction "C_C") (pintype "passive"))
      (node (ref "R14") (pin "2") (pinfunction "2_2") (pintype "passive"))
    )
    (net (code "84") (name "Net-(LED3-PadC)") (class "Default")
      (node (ref "LED3") (pin "C") (pinfunction "C_C") (pintype "passive"))
      (node (ref "R23") (pin "2") (pinfunction "2_2") (pintype "passive"))
    )
    (net (code "85") (name "Net-(R15-Pad2)") (class "Default")
      (node (ref "R15") (pin "2") (pinfunction "2_2") (pintype "passive"))
      (node (ref "R17") (pin "1") (pinfunction "1_1") (pintype "passive"))
      (node (ref "U$1") (pin "D-") (pinfunction "D-_D-") (pintype "bidirectional"))
    )
    (net (code "86") (name "Net-(R16-Pad2)") (class "Default")
      (node (ref "R16") (pin "2") (pinfunction "2_2") (pintype "passive"))
      (node (ref "U$1") (pin "D+") (pinfunction "D+_D+") (pintype "bidirectional"))
    )
    (net (code "87") (name "unconnected-(ETH1-NC-Pad7)") (class "Default")
      (node (ref "ETH1") (pin "7") (pinfunction "NC_7") (pintype "passive"))
    )
    (net (code "88") (name "unconnected-(ETH2-NC-Pad7)") (class "Default")
      (node (ref "ETH2") (pin "7") (pinfunction "NC_7") (pintype "passive"))
    )
    (net (code "89") (name "unconnected-(ETH3-NC-Pad7)") (class "Default")
      (node (ref "ETH3") (pin "7") (pinfunction "NC_7") (pintype "passive"))
    )
    (net (code "90") (name "unconnected-(ETH4-NC-Pad7)") (class "Default")
      (node (ref "ETH4") (pin "7") (pinfunction "NC_7") (pintype "passive"))
    )
    (net (code "91") (name "unconnected-(ETH5-NC-Pad7)") (class "Default")
      (node (ref "ETH5") (pin "7") (pinfunction "NC_7") (pintype "passive"))
    )
    (net (code "92") (name "unconnected-(IC1-FXSD4-Pad39)") (class "Default")
      (node (ref "IC1") (pin "39") (pinfunction "FXSD4_39") (pintype "bidirectional"))
    )
    (net (code "93") (name "unconnected-(IC1-FXSD5-Pad38)") (class "Default")
      (node (ref "IC1") (pin "38") (pinfunction "FXSD5_38") (pintype "bidirectional"))
    )
    (net (code "94") (name "unconnected-(IC1-MDC-Pad107)") (class "Default")
      (node (ref "IC1") (pin "107") (pinfunction "MDC_107") (pintype "bidirectional"))
    )
    (net (code "95") (name "unconnected-(IC1-MDI-XDIS-Pad1)") (class "Default")
      (node (ref "IC1") (pin "1") (pinfunction "MDI-XDIS_1") (pintype "bidirectional"))
    )
    (net (code "96") (name "unconnected-(IC1-MDIO-Pad108)") (class "Default")
      (node (ref "IC1") (pin "108") (pinfunction "MDIO_108") (pintype "bidirectional"))
    )
    (net (code "97") (name "unconnected-(IC1-MUX1-Pad45)") (class "Default")
      (node (ref "IC1") (pin "45") (pinfunction "MUX1_45") (pintype "bidirectional"))
    )
    (net (code "98") (name "unconnected-(IC1-MUX2-Pad46)") (class "Default")
      (node (ref "IC1") (pin "46") (pinfunction "MUX2_46") (pintype "bidirectional"))
    )
    (net (code "99") (name "unconnected-(IC1-NC-Pad120)") (class "Default")
      (node (ref "IC1") (pin "120") (pinfunction "NC_120") (pintype "bidirectional"))
    )
    (net (code "100") (name "unconnected-(IC1-PCOL-Pad68)") (class "Default")
      (node (ref "IC1") (pin "68") (pinfunction "PCOL_68") (pintype "bidirectional"))
    )
    (net (code "101") (name "unconnected-(IC1-PCRS-Pad67)") (class "Default")
      (node (ref "IC1") (pin "67") (pinfunction "PCRS_67") (pintype "bidirectional"))
    )
    (net (code "102") (name "unconnected-(IC1-PMRXC-Pad60)") (class "Default")
      (node (ref "IC1") (pin "60") (pinfunction "PMRXC_60") (pintype "bidirectional"))
    )
    (net (code "103") (name "unconnected-(IC1-PMRXD0-Pad65)") (class "Default")
      (node (ref "IC1") (pin "65") (pinfunction "PMRXD0_65") (pintype "bidirectional"))
    )
    (net (code "104") (name "unconnected-(IC1-PMRXD1-Pad64)") (class "Default")
      (node (ref "IC1") (pin "64") (pinfunction "PMRXD1_64") (pintype "bidirectional"))
    )
    (net (code "105") (name "unconnected-(IC1-PMRXD2-Pad63)") (class "Default")
      (node (ref "IC1") (pin "63") (pinfunction "PMRXD2_63") (pintype "bidirectional"))
    )
    (net (code "106") (name "unconnected-(IC1-PMRXD3-Pad62)") (class "Default")
      (node (ref "IC1") (pin "62") (pinfunction "PMRXD3_62") (pintype "bidirectional"))
    )
    (net (code "107") (name "unconnected-(IC1-PMRXDV-Pad61)") (class "Default")
      (node (ref "IC1") (pin "61") (pinfunction "PMRXDV_61") (pintype "bidirectional"))
    )
    (net (code "108") (name "unconnected-(IC1-PMRXER-Pad66)") (class "Default")
      (node (ref "IC1") (pin "66") (pinfunction "PMRXER_66") (pintype "bidirectional"))
    )
    (net (code "109") (name "unconnected-(IC1-PMTXC-Pad57)") (class "Default")
      (node (ref "IC1") (pin "57") (pinfunction "PMTXC_57") (pintype "bidirectional"))
    )
    (net (code "110") (name "unconnected-(IC1-PMTXD0-Pad55)") (class "Default")
      (node (ref "IC1") (pin "55") (pinfunction "PMTXD0_55") (pintype "bidirectional"))
    )
    (net (code "111") (name "unconnected-(IC1-PMTXD1-Pad54)") (class "Default")
      (node (ref "IC1") (pin "54") (pinfunction "PMTXD1_54") (pintype "bidirectional"))
    )
    (net (code "112") (name "unconnected-(IC1-PMTXD2-Pad53)") (class "Default")
      (node (ref "IC1") (pin "53") (pinfunction "PMTXD2_53") (pintype "bidirectional"))
    )
    (net (code "113") (name "unconnected-(IC1-PMTXD3-Pad52)") (class "Default")
      (node (ref "IC1") (pin "52") (pinfunction "PMTXD3_52") (pintype "bidirectional"))
    )
    (net (code "114") (name "unconnected-(IC1-PMTXEN-Pad51)") (class "Default")
      (node (ref "IC1") (pin "51") (pinfunction "PMTXEN_51") (pintype "bidirectional"))
    )
    (net (code "115") (name "unconnected-(IC1-PMTXER-Pad56)") (class "Default")
      (node (ref "IC1") (pin "56") (pinfunction "PMTXER_56") (pintype "bidirectional"))
    )
    (net (code "116") (name "unconnected-(IC1-PWRDN_N-Pad47)") (class "Default")
      (node (ref "IC1") (pin "47") (pinfunction "PWRDN_N_47") (pintype "bidirectional"))
    )
    (net (code "117") (name "unconnected-(IC1-RESERVED-Pad48)") (class "Default")
      (node (ref "IC1") (pin "48") (pinfunction "RESERVED_48") (pintype "bidirectional"))
    )
    (net (code "118") (name "unconnected-(IC1-SCANEN-Pad119)") (class "Default")
      (node (ref "IC1") (pin "119") (pinfunction "SCANEN_119") (pintype "bidirectional"))
    )
    (net (code "119") (name "unconnected-(IC1-SCOL-Pad84)") (class "Default")
      (node (ref "IC1") (pin "84") (pinfunction "SCOL_84") (pintype "bidirectional"))
    )
    (net (code "120") (name "unconnected-(IC1-SCRS-Pad85)") (class "Default")
      (node (ref "IC1") (pin "85") (pinfunction "SCRS_85") (pintype "bidirectional"))
    )
    (net (code "121") (name "unconnected-(IC1-SMRXC-Pad78)") (class "Default")
      (node (ref "IC1") (pin "78") (pinfunction "SMRXC_78") (pintype "bidirectional"))
    )
    (net (code "122") (name "unconnected-(IC1-SMRXD0-Pad83)") (class "Default")
      (node (ref "IC1") (pin "83") (pinfunction "SMRXD0_83") (pintype "bidirectional"))
    )
    (net (code "123") (name "unconnected-(IC1-SMRXD1-Pad82)") (class "Default")
      (node (ref "IC1") (pin "82") (pinfunction "SMRXD1_82") (pintype "bidirectional"))
    )
    (net (code "124") (name "unconnected-(IC1-SMRXD2-Pad81)") (class "Default")
      (node (ref "IC1") (pin "81") (pinfunction "SMRXD2_81") (pintype "bidirectional"))
    )
    (net (code "125") (name "unconnected-(IC1-SMRXD3-Pad80)") (class "Default")
      (node (ref "IC1") (pin "80") (pinfunction "SMRXD3_80") (pintype "bidirectional"))
    )
    (net (code "126") (name "unconnected-(IC1-SMRXDV-Pad79)") (class "Default")
      (node (ref "IC1") (pin "79") (pinfunction "SMRXDV_79") (pintype "bidirectional"))
    )
    (net (code "127") (name "unconnected-(IC1-SMTXC-Pad75)") (class "Default")
      (node (ref "IC1") (pin "75") (pinfunction "SMTXC_75") (pintype "bidirectional"))
    )
    (net (code "128") (name "unconnected-(IC1-SMTXD0-Pad73)") (class "Default")
      (node (ref "IC1") (pin "73") (pinfunction "SMTXD0_73") (pintype "bidirectional"))
    )
    (net (code "129") (name "unconnected-(IC1-SMTXD1-Pad72)") (class "Default")
      (node (ref "IC1") (pin "72") (pinfunction "SMTXD1_72") (pintype "bidirectional"))
    )
    (net (code "130") (name "unconnected-(IC1-SMTXD2-Pad71)") (class "Default")
      (node (ref "IC1") (pin "71") (pinfunction "SMTXD2_71") (pintype "bidirectional"))
    )
    (net (code "131") (name "unconnected-(IC1-SMTXD3-Pad70)") (class "Default")
      (node (ref "IC1") (pin "70") (pinfunction "SMTXD3_70") (pintype "bidirectional"))
    )
    (net (code "132") (name "unconnected-(IC1-SMTXEN-Pad69)") (class "Default")
      (node (ref "IC1") (pin "69") (pinfunction "SMTXEN_69") (pintype "bidirectional"))
    )
    (net (code "133") (name "unconnected-(IC1-SMTXER-Pad74)") (class "Default")
      (node (ref "IC1") (pin "74") (pinfunction "SMTXER_74") (pintype "bidirectional"))
    )
    (net (code "134") (name "unconnected-(IC1-TEST2-Pad128)") (class "Default")
      (node (ref "IC1") (pin "128") (pinfunction "TEST2_128") (pintype "bidirectional"))
    )
    (net (code "135") (name "unconnected-(IC1-TESTEN-Pad118)") (class "Default")
      (node (ref "IC1") (pin "118") (pinfunction "TESTEN_118") (pintype "bidirectional"))
    )
    (net (code "136") (name "unconnected-(IC5-ADC6-Pad19)") (class "Default")
      (node (ref "IC5") (pin "19") (pinfunction "ADC6_19") (pintype "passive"))
    )
    (net (code "137") (name "unconnected-(IC5-ADC7-Pad22)") (class "Default")
      (node (ref "IC5") (pin "22") (pinfunction "ADC7_22") (pintype "passive"))
    )
    (net (code "138") (name "unconnected-(IC5-AREF-Pad20)") (class "Default")
      (node (ref "IC5") (pin "20") (pinfunction "AREF_20") (pintype "passive"))
    )
    (net (code "139") (name "unconnected-(IC5-PB0(ICP1{slash}CLKO{slash}PCINT0)-Pad12)") (class "Default")
      (node (ref "IC5") (pin "12") (pinfunction "PB0(ICP1/CLKO/PCINT0)_12") (pintype "bidirectional"))
    )
    (net (code "140") (name "unconnected-(IC5-PB1(OC1A{slash}PCINT1)-Pad13)") (class "Default")
      (node (ref "IC5") (pin "13") (pinfunction "PB1(OC1A/PCINT1)_13") (pintype "bidirectional"))
    )
    (net (code "141") (name "unconnected-(IC5-PC0(ADC0{slash}PCINT8)-Pad23)") (class "Default")
      (node (ref "IC5") (pin "23") (pinfunction "PC0(ADC0/PCINT8)_23") (pintype "bidirectional"))
    )
    (net (code "142") (name "unconnected-(IC5-PC2(ADC2{slash}PCINT10)-Pad25)") (class "Default")
      (node (ref "IC5") (pin "25") (pinfunction "PC2(ADC2/PCINT10)_25") (pintype "bidirectional"))
    )
    (net (code "143") (name "unconnected-(IC5-PC3(ADC3{slash}PCINT11)-Pad26)") (class "Default")
      (node (ref "IC5") (pin "26") (pinfunction "PC3(ADC3/PCINT11)_26") (pintype "bidirectional"))
    )
    (net (code "144") (name "unconnected-(IC5-PC4(ADC4{slash}SDA{slash}PCINT12)-Pad27)") (class "Default")
      (node (ref "IC5") (pin "27") (pinfunction "PC4(ADC4/SDA/PCINT12)_27") (pintype "bidirectional"))
    )
    (net (code "145") (name "unconnected-(IC5-PC5(ADC5{slash}SCL{slash}PCINT13)-Pad28)") (class "Default")
      (node (ref "IC5") (pin "28") (pinfunction "PC5(ADC5/SCL/PCINT13)_28") (pintype "bidirectional"))
    )
    (net (code "146") (name "unconnected-(IC5-PD0(RXD{slash}PCINT16)-Pad30)") (class "Default")
      (node (ref "IC5") (pin "30") (pinfunction "PD0(RXD/PCINT16)_30") (pintype "bidirectional"))
    )
    (net (code "147") (name "unconnected-(IC5-PD5(T1{slash}OC0B{slash}PCINT21)-Pad9)") (class "Default")
      (node (ref "IC5") (pin "9") (pinfunction "PD5(T1/OC0B/PCINT21)_9") (pintype "bidirectional"))
    )
    (net (code "148") (name "unconnected-(IC5-PD6(AIN0{slash}OC0A{slash}PCINT22)-Pad10)") (class "Default")
      (node (ref "IC5") (pin "10") (pinfunction "PD6(AIN0/OC0A/PCINT22)_10") (pintype "bidirectional"))
    )
    (net (code "149") (name "unconnected-(IC5-PD7(AIN1{slash}PCINT23)-Pad11)") (class "Default")
      (node (ref "IC5") (pin "11") (pinfunction "PD7(AIN1/PCINT23)_11") (pintype "bidirectional"))
    )
    (net (code "150") (name "unconnected-(U$1-PadID)") (class "Default")
      (node (ref "U$1") (pin "ID") (pinfunction "ID_ID") (pintype "bidirectional"))
    )
  )
)
